# power-converter.net
KiCad netlist of a schematic drawn in Altium Designer
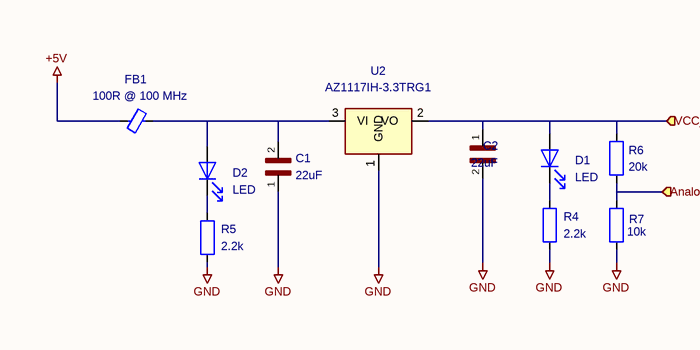
[diagram p0: power-converter.SchDoc]

(export (version "E")
  (design (tool "Eeschema 10.0.6"))
  (components
    (comp (ref "C1") (value "22uF") (libsource (lib "Daughterboard_Symbols") (part "CL10B104KB8NNNL")))
    (comp (ref "C2") (value "22uF") (libsource (lib "") (part "CL10B104KB8NNNL_1")))
    (comp (ref "D1") (value "LED") (libsource (lib "Device") (part "LED")))
    (comp (ref "D2") (value "LED") (libsource (lib "Device") (part "LED")))
    (comp (ref "FB1") (value "100R @ 100 MHz") (libsource (lib "Device") (part "FerriteBead_Small")))
    (comp (ref "R4") (value "2.2k") (libsource (lib "Device") (part "R")))
    (comp (ref "R5") (value "2.2k") (libsource (lib "Device") (part "R")))
    (comp (ref "R6") (value "20k") (libsource (lib "Device") (part "R")))
    (comp (ref "R7") (value "10k") (libsource (lib "Device") (part "R")))
    (comp (ref "U2") (value "AZ1117IH-3.3TRG1") (libsource (lib "Regulator_Linear") (part "AZ1117-3.3")))
  )
  (nets
    (net (code "1") (name "+5V") (class "Default")
      (node (ref "FB1") (pin "2") (pinfunction "2_2") (pintype "passive"))
    )
    (net (code "2") (name "/Analog Output Voltage") (class "Default")
      (node (ref "R6") (pin "2") (pinfunction "2_2") (pintype "passive"))
      (node (ref "R7") (pin "1") (pinfunction "1_1") (pintype "passive"))
    )
    (net (code "3") (name "/VCC_3V3") (class "Default")
      (node (ref "C2") (pin "1") (pinfunction "1_1") (pintype "passive"))
      (node (ref "D1") (pin "2") (pinfunction "A_2") (pintype "passive"))
      (node (ref "R6") (pin "1") (pinfunction "1_1") (pintype "passive"))
      (node (ref "U2") (pin "2") (pinfunction "VO_2") (pintype "passive"))
    )
    (net (code "4") (name "GND") (class "Default")
      (node (ref "C1") (pin "1") (pinfunction "1_1") (pintype "passive"))
      (node (ref "C2") (pin "2") (pinfunction "2_2") (pintype "passive"))
      (node (ref "R4") (pin "2") (pinfunction "2_2") (pintype "passive"))
      (node (ref "R5") (pin "2") (pinfunction "2_2") (pintype "passive"))
      (node (ref "R7") (pin "2") (pinfunction "2_2") (pintype "passive"))
      (node (ref "U2") (pin "1") (pinfunction "GND_1") (pintype "passive"))
    )
    (net (code "5") (name "Net-(D1-K)") (class "Default")
      (node (ref "D1") (pin "1") (pinfunction "K_1") (pintype "passive"))
      (node (ref "R4") (pin "1") (pinfunction "1_1") (pintype "passive"))
    )
    (net (code "6") (name "Net-(D2-A)") (class "Default")
      (node (ref "C1") (pin "2") (pinfunction "2_2") (pintype "passive"))
      (node (ref "D2") (pin "2") (pinfunction "A_2") (pintype "passive"))
      (node (ref "FB1") (pin "1") (pinfunction "1_1") (pintype "passive"))
      (node (ref "U2") (pin "3") (pinfunction "VI_3") (pintype "passive"))
    )
    (net (code "7") (name "Net-(D2-K)") (class "Default")
      (node (ref "D2") (pin "1") (pinfunction "K_1") (pintype "passive"))
      (node (ref "R5") (pin "1") (pinfunction "1_1") (pintype "passive"))
    )
  )
)
